# IoT-Mailbox-Guard.net
KiCad netlist of a schematic drawn in EAGLE
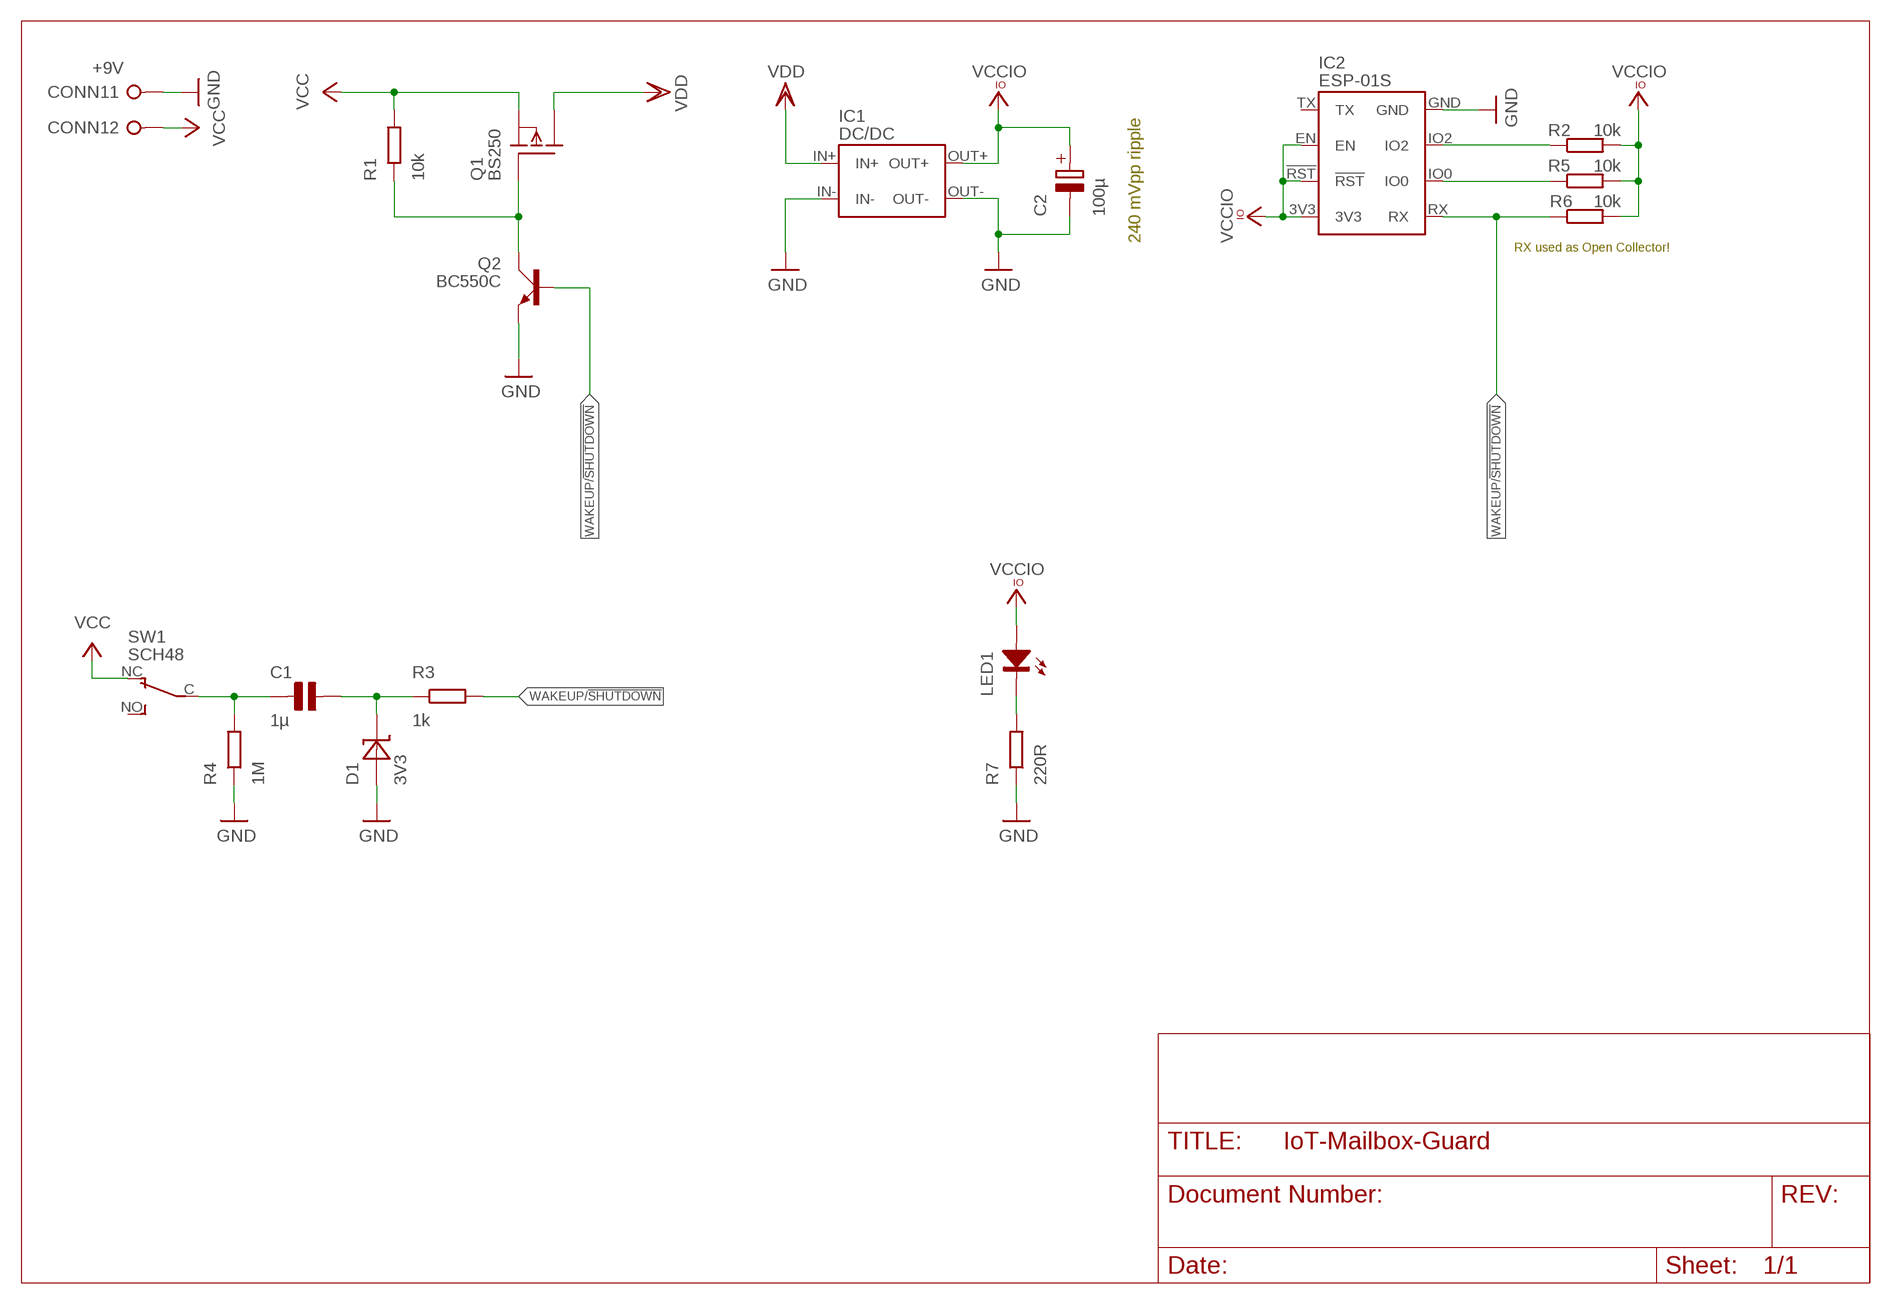
[diagram p0: schematic, sheet 1]

(export (version "E")
  (design (tool "Eeschema 10.0.6"))
  (components
    (comp (ref "C1")
      (value "1µ")
      (footprint "eagle-import:GENERIC-5.08")
      (libsource (lib "eagle-import") (part "C-5,08"))
    )
    (comp (ref "C2")
      (value "100µ")
      (footprint "eagle-import:ELKO-2.54-6MM")
      (libsource (lib "eagle-import") (part "ELKO-2.54-6MM"))
    )
    (comp (ref "CONN1")
      (value "+9V")
      (footprint "eagle-import:WAGO-2")
      (libsource (lib "eagle-import") (part "WAGO-2"))
    )
    (comp (ref "D1")
      (value "3V3")
      (footprint "eagle-import:DIODE-7.62")
      (libsource (lib "eagle-import") (part "DIODE-ZENER-7.62"))
    )
    (comp (ref "IC1")
      (value "DC/DC")
      (footprint "eagle-import:DC_DC-MINI360-BUCK")
      (libsource (lib "eagle-import") (part "DC/DC"))
    )
    (comp (ref "IC2")
      (value "ESP-01S")
      (footprint "eagle-import:ESP-01S")
      (libsource (lib "eagle-import") (part "ESP-01S"))
    )
    (comp (ref "LED1")
      (value "LED-3")
      (footprint "eagle-import:LED-3")
      (libsource (lib "eagle-import") (part "LED-3"))
    )
    (comp (ref "Q1")
      (value "BS250")
      (footprint "eagle-import:TO-92")
      (libsource (lib "eagle-import") (part "PMOSFET-TO-92"))
    )
    (comp (ref "Q2")
      (value "BC550C")
      (footprint "eagle-import:TO-92")
      (libsource (lib "eagle-import") (part "NPN-TO-92"))
    )
    (comp (ref "R1")
      (value "10k")
      (footprint "eagle-import:GENERIC-7.62")
      (libsource (lib "eagle-import") (part "R-7,62"))
    )
    (comp (ref "R2")
      (value "10k")
      (footprint "eagle-import:GENERIC-7.62")
      (libsource (lib "eagle-import") (part "R-7,62"))
    )
    (comp (ref "R3")
      (value "1k")
      (footprint "eagle-import:GENERIC-7.62")
      (libsource (lib "eagle-import") (part "R-7,62"))
    )
    (comp (ref "R4")
      (value "1M")
      (footprint "eagle-import:GENERIC-7.62")
      (libsource (lib "eagle-import") (part "R-7,62"))
    )
    (comp (ref "R5")
      (value "10k")
      (footprint "eagle-import:GENERIC-7.62")
      (libsource (lib "eagle-import") (part "R-7,62"))
    )
    (comp (ref "R6")
      (value "10k")
      (footprint "eagle-import:GENERIC-7.62")
      (libsource (lib "eagle-import") (part "R-7,62"))
    )
    (comp (ref "R7")
      (value "220R")
      (footprint "eagle-import:GENERIC-7.62")
      (libsource (lib "eagle-import") (part "R-7,62"))
    )
    (comp (ref "SW1")
      (value "SCH48")
      (footprint "eagle-import:MICROSWITCH-SCH48")
      (libsource (lib "eagle-import") (part "MICROSWITCH-SCH48"))
    )
  )
  (nets
    (net (code "1") (name "/WAKEUP{slash}~{SHUTDOWN}") (class "Default")
      (node (ref "IC2") (pin "RX") (pinfunction "RX_RX") (pintype "bidirectional"))
      (node (ref "Q2") (pin "2") (pinfunction "B_2") (pintype "passive"))
      (node (ref "R3") (pin "2") (pinfunction "2_2") (pintype "passive"))
      (node (ref "R6") (pin "1") (pinfunction "1_1") (pintype "passive"))
    )
    (net (code "2") (name "GND") (class "Default")
      (node (ref "C2") (pin "-") (pinfunction "-_-") (pintype "passive"))
      (node (ref "CONN1") (pin "1") (pinfunction "KL_1") (pintype "passive"))
      (node (ref "D1") (pin "A") (pinfunction "A_A") (pintype "passive"))
      (node (ref "IC1") (pin "IN-") (pinfunction "IN-_IN-") (pintype "power_in"))
      (node (ref "IC1") (pin "OUT-") (pinfunction "OUT-_OUT-") (pintype "power_in"))
      (node (ref "IC2") (pin "GND") (pinfunction "GND_GND") (pintype "power_in"))
      (node (ref "Q2") (pin "3") (pinfunction "E_3") (pintype "passive"))
      (node (ref "R4") (pin "1") (pinfunction "1_1") (pintype "passive"))
      (node (ref "R7") (pin "1") (pinfunction "1_1") (pintype "passive"))
    )
    (net (code "3") (name "Net-(C1-Pad2)") (class "Default")
      (node (ref "C1") (pin "2") (pinfunction "2_2") (pintype "passive"))
      (node (ref "D1") (pin "C") (pinfunction "C_C") (pintype "passive"))
      (node (ref "R3") (pin "1") (pinfunction "1_1") (pintype "passive"))
    )
    (net (code "4") (name "Net-(IC2-PadIO0)") (class "Default")
      (node (ref "IC2") (pin "IO0") (pinfunction "IO0_IO0") (pintype "bidirectional"))
      (node (ref "R5") (pin "1") (pinfunction "1_1") (pintype "passive"))
    )
    (net (code "5") (name "Net-(IC2-PadIO2)") (class "Default")
      (node (ref "IC2") (pin "IO2") (pinfunction "IO2_IO2") (pintype "bidirectional"))
      (node (ref "R2") (pin "1") (pinfunction "1_1") (pintype "passive"))
    )
    (net (code "6") (name "Net-(LED1-C)") (class "Default")
      (node (ref "LED1") (pin "K") (pinfunction "C_K") (pintype "passive"))
      (node (ref "R7") (pin "2") (pinfunction "2_2") (pintype "passive"))
    )
    (net (code "7") (name "Net-(Q1-G)") (class "Default")
      (node (ref "Q1") (pin "2") (pinfunction "G_2") (pintype "passive"))
      (node (ref "Q2") (pin "1") (pinfunction "C_1") (pintype "passive"))
      (node (ref "R1") (pin "1") (pinfunction "1_1") (pintype "passive"))
    )
    (net (code "8") (name "Net-(SW1-COM)") (class "Default")
      (node (ref "C1") (pin "1") (pinfunction "1_1") (pintype "passive"))
      (node (ref "R4") (pin "2") (pinfunction "2_2") (pintype "passive"))
      (node (ref "SW1") (pin "C") (pinfunction "COM_C") (pintype "passive"))
    )
    (net (code "9") (name "VCC") (class "Default")
      (node (ref "CONN1") (pin "2") (pinfunction "KL_2") (pintype "passive"))
      (node (ref "Q1") (pin "3") (pinfunction "S_3") (pintype "passive"))
      (node (ref "R1") (pin "2") (pinfunction "2_2") (pintype "passive"))
      (node (ref "SW1") (pin "NC") (pinfunction "NC_NC") (pintype "passive"))
    )
    (net (code "10") (name "VCCIO") (class "Default")
      (node (ref "C2") (pin "+") (pinfunction "+_+") (pintype "passive"))
      (node (ref "IC1") (pin "OUT+") (pinfunction "OUT+_OUT+") (pintype "power_in"))
      (node (ref "IC2") (pin "!RST") (pinfunction "~{RST}_!RST") (pintype "input"))
      (node (ref "IC2") (pin "3V3") (pinfunction "3V3_3V3") (pintype "power_in"))
      (node (ref "IC2") (pin "EN") (pinfunction "EN_EN") (pintype "input"))
      (node (ref "LED1") (pin "A") (pinfunction "A_A") (pintype "passive"))
      (node (ref "R2") (pin "2") (pinfunction "2_2") (pintype "passive"))
      (node (ref "R5") (pin "2") (pinfunction "2_2") (pintype "passive"))
      (node (ref "R6") (pin "2") (pinfunction "2_2") (pintype "passive"))
    )
    (net (code "11") (name "VDD") (class "Default")
      (node (ref "IC1") (pin "IN+") (pinfunction "IN+_IN+") (pintype "power_in"))
      (node (ref "Q1") (pin "1") (pinfunction "D_1") (pintype "passive"))
    )
    (net (code "12") (name "unconnected-(IC2-PadTX)") (class "Default")
      (node (ref "IC2") (pin "TX") (pinfunction "TX_TX") (pintype "bidirectional"))
    )
    (net (code "13") (name "unconnected-(SW1-PadNO)") (class "Default")
      (node (ref "SW1") (pin "NO") (pinfunction "NO_NO") (pintype "passive"))
    )
  )
)
